# SolarMppt.net
KiCad netlist of a schematic drawn in Altium Designer
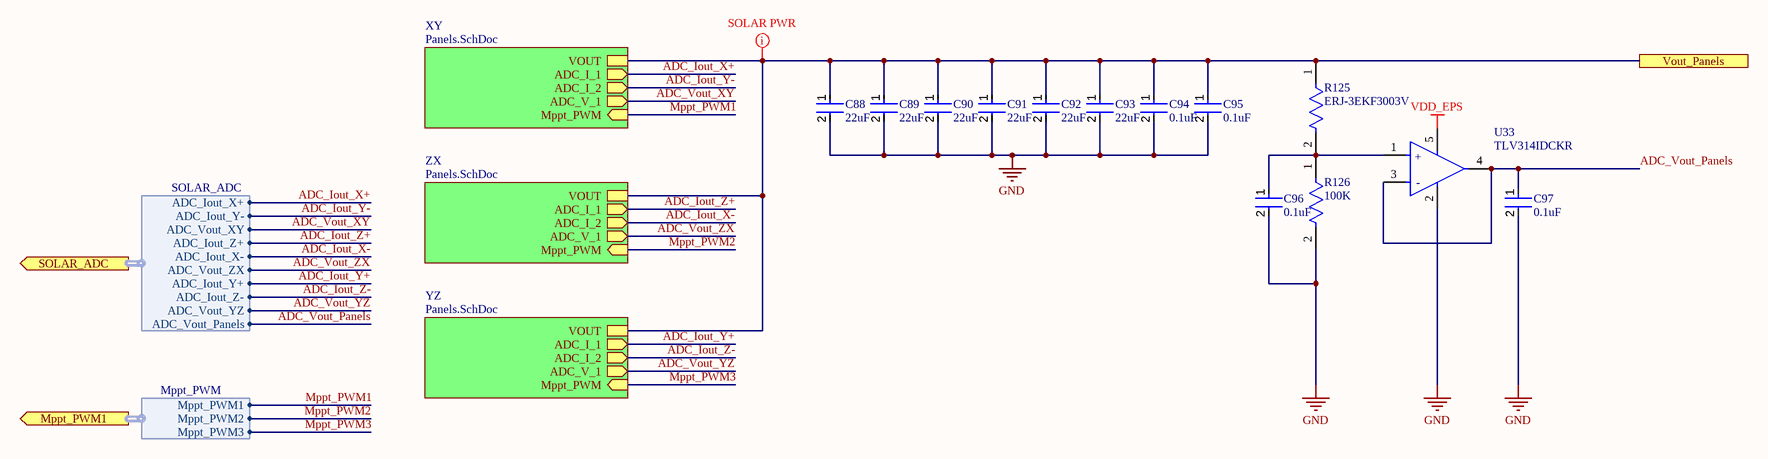
[diagram p0: SolarMppt.SchDoc]

(export (version "E")
  (design (tool "Eeschema 10.0.6"))
  (components
    (comp (ref "C88")
      (value "22uF")
      (footprint "FP-GRM21B-0_2-e0_2_0_7-IPC_C")
      (description "Chip Multilayer Ceramic Capacitors for General Purpose, 0805, 22uF, X7T, +22%/-33%, 20%, 10V")
      (fields (field (name "VOLTAGE") "10V") (field (name "TOLERANCE") "20%"))
      (libsource (lib "Altium Content Vault") (part "b4654b650e69147ec39a6b967a45e02"))
    )
    (comp (ref "C89")
      (value "22uF")
      (footprint "FP-GRM21B-0_2-e0_2_0_7-IPC_C")
      (description "Chip Multilayer Ceramic Capacitors for General Purpose, 0805, 22uF, X7T, +22%/-33%, 20%, 10V")
      (fields (field (name "VOLTAGE") "10V") (field (name "TOLERANCE") "20%"))
      (libsource (lib "Altium Content Vault") (part "b4654b650e69147ec39a6b967a45e02"))
    )
    (comp (ref "C90")
      (value "22uF")
      (footprint "FP-GRM21B-0_2-e0_2_0_7-IPC_C")
      (description "Chip Multilayer Ceramic Capacitors for General Purpose, 0805, 22uF, X7T, +22%/-33%, 20%, 10V")
      (fields (field (name "VOLTAGE") "10V") (field (name "TOLERANCE") "20%"))
      (libsource (lib "Altium Content Vault") (part "b4654b650e69147ec39a6b967a45e02"))
    )
    (comp (ref "C91")
      (value "22uF")
      (footprint "FP-GRM21B-0_2-e0_2_0_7-IPC_C")
      (description "Chip Multilayer Ceramic Capacitors for General Purpose, 0805, 22uF, X7T, +22%/-33%, 20%, 10V")
      (fields (field (name "VOLTAGE") "10V") (field (name "TOLERANCE") "20%"))
      (libsource (lib "Altium Content Vault") (part "b4654b650e69147ec39a6b967a45e02"))
    )
    (comp (ref "C92")
      (value "22uF")
      (footprint "FP-GRM21B-0_2-e0_2_0_7-IPC_C")
      (description "Chip Multilayer Ceramic Capacitors for General Purpose, 0805, 22uF, X7T, +22%/-33%, 20%, 10V")
      (fields (field (name "VOLTAGE") "10V") (field (name "TOLERANCE") "20%"))
      (libsource (lib "Altium Content Vault") (part "b4654b650e69147ec39a6b967a45e02"))
    )
    (comp (ref "C93")
      (value "22uF")
      (footprint "FP-GRM21B-0_2-e0_2_0_7-IPC_C")
      (description "Chip Multilayer Ceramic Capacitors for General Purpose, 0805, 22uF, X7T, +22%/-33%, 20%, 10V")
      (fields (field (name "VOLTAGE") "10V") (field (name "TOLERANCE") "20%"))
      (libsource (lib "Altium Content Vault") (part "b4654b650e69147ec39a6b967a45e02"))
    )
    (comp (ref "C94")
      (value "0.1uF")
      (footprint "FP-C0603C-CF-MFG")
      (description "CAP CER 0.1UF 16V X7R 0603")
      (fields
        (field (name "OCTOPART") "https://octopart.com/c0603c104j4ractu-kemet-102515")
        (field (name "MANUFACTURER") "KEMET")
      )
      (libsource (lib "Altium Content Vault") (part "b4654b650e69147ec39a6b967a45e02"))
    )
    (comp (ref "C95")
      (value "0.1uF")
      (footprint "FP-C0603C-CF-MFG")
      (description "CAP CER 0.1UF 16V X7R 0603")
      (fields
        (field (name "OCTOPART") "https://octopart.com/c0603c104j4ractu-kemet-102515")
        (field (name "MANUFACTURER") "KEMET")
      )
      (libsource (lib "Altium Content Vault") (part "b4654b650e69147ec39a6b967a45e02"))
    )
    (comp (ref "C96")
      (value "0.1uF")
      (footprint "FP-C0603C-CF-MFG")
      (description "CAP CER 0.1UF 50V X7R 0603")
      (fields (field (name "TOLERANCE") "0.1") (field (name "MANUFACTURER") "KEMET"))
      (libsource (lib "Altium Content Vault") (part "b4654b650e69147ec39a6b967a45e02"))
    )
    (comp (ref "C97")
      (value "0.1uF")
      (footprint "FP-C0603C-CF-MFG")
      (description "CAP CER 0.1UF 50V X7R 0603")
      (fields (field (name "TOLERANCE") "0.1") (field (name "MANUFACTURER") "KEMET"))
      (libsource (lib "Altium Content Vault") (part "b4654b650e69147ec39a6b967a45e02"))
    )
    (comp (ref "R125")
      (value "ERJ-3EKF3003V")
      (footprint "FP-ERJ3EK-MFG")
      (fields (field (name "TOLERANCE") "1%"))
      (libsource (lib "Altium Content Vault") (part "1029c3af85768c4190bb7ad29bc67b5"))
    )
    (comp (ref "R126")
      (value "100K")
      (footprint "FP-ERA3A-MFG")
      (fields (field (name "TOLERANCE") "0.1%"))
      (libsource (lib "Altium Content Vault") (part "1029c3af85768c4190bb7ad29bc67b5"))
    )
    (comp (ref "U33")
      (value "TLV314IDCKR")
      (footprint "FP-DCK0005A-MFG")
      (description "IC CMOS 1 CIRCUIT SC70-5")
      (libsource (lib "Altium Content Vault") (part "000f5c41575af8b8d083a31a5be8140"))
    )
  )
  (nets
    (net (code "9") (name "/ADC_Vout_Panels") (class "Default")
      (node (ref "C97") (pin "1") (pinfunction "1_1") (pintype "passive"))
      (node (ref "U33") (pin "3") (pinfunction "-IN_3") (pintype "tri_state"))
      (node (ref "U33") (pin "4") (pinfunction "OUT_4") (pintype "passive"))
    )
    (net (code "16") (name "/Vout_Panels") (class "Default")
      (node (ref "C88") (pin "1") (pinfunction "1_1") (pintype "passive"))
      (node (ref "C89") (pin "1") (pinfunction "1_1") (pintype "passive"))
      (node (ref "C90") (pin "1") (pinfunction "1_1") (pintype "passive"))
      (node (ref "C91") (pin "1") (pinfunction "1_1") (pintype "passive"))
      (node (ref "C92") (pin "1") (pinfunction "1_1") (pintype "passive"))
      (node (ref "C93") (pin "1") (pinfunction "1_1") (pintype "passive"))
      (node (ref "C94") (pin "1") (pinfunction "1_1") (pintype "passive"))
      (node (ref "C95") (pin "1") (pinfunction "1_1") (pintype "passive"))
      (node (ref "R125") (pin "1") (pinfunction "1_1") (pintype "passive"))
    )
    (net (code "19") (name "GND") (class "Default")
      (node (ref "C88") (pin "2") (pinfunction "2_2") (pintype "passive"))
      (node (ref "C89") (pin "2") (pinfunction "2_2") (pintype "passive"))
      (node (ref "C90") (pin "2") (pinfunction "2_2") (pintype "passive"))
      (node (ref "C91") (pin "2") (pinfunction "2_2") (pintype "passive"))
      (node (ref "C92") (pin "2") (pinfunction "2_2") (pintype "passive"))
      (node (ref "C93") (pin "2") (pinfunction "2_2") (pintype "passive"))
      (node (ref "C94") (pin "2") (pinfunction "2_2") (pintype "passive"))
      (node (ref "C95") (pin "2") (pinfunction "2_2") (pintype "passive"))
      (node (ref "C96") (pin "2") (pinfunction "2_2") (pintype "passive"))
      (node (ref "C97") (pin "2") (pinfunction "2_2") (pintype "passive"))
      (node (ref "R126") (pin "2") (pinfunction "2_2") (pintype "passive"))
      (node (ref "U33") (pin "2") (pinfunction "V-_2") (pintype "power_in"))
    )
    (net (code "20") (name "Net-(U33-+IN)") (class "Default")
      (node (ref "C96") (pin "1") (pinfunction "1_1") (pintype "passive"))
      (node (ref "R125") (pin "2") (pinfunction "2_2") (pintype "passive"))
      (node (ref "R126") (pin "1") (pinfunction "1_1") (pintype "passive"))
      (node (ref "U33") (pin "1") (pinfunction "+IN_1") (pintype "tri_state"))
    )
    (net (code "21") (name "VDD_EPS") (class "Default")
      (node (ref "U33") (pin "5") (pinfunction "V+_5") (pintype "power_in"))
    )
  )
)
